# aixplorer_lpc111x.net
KiCad netlist of a schematic drawn in EAGLE
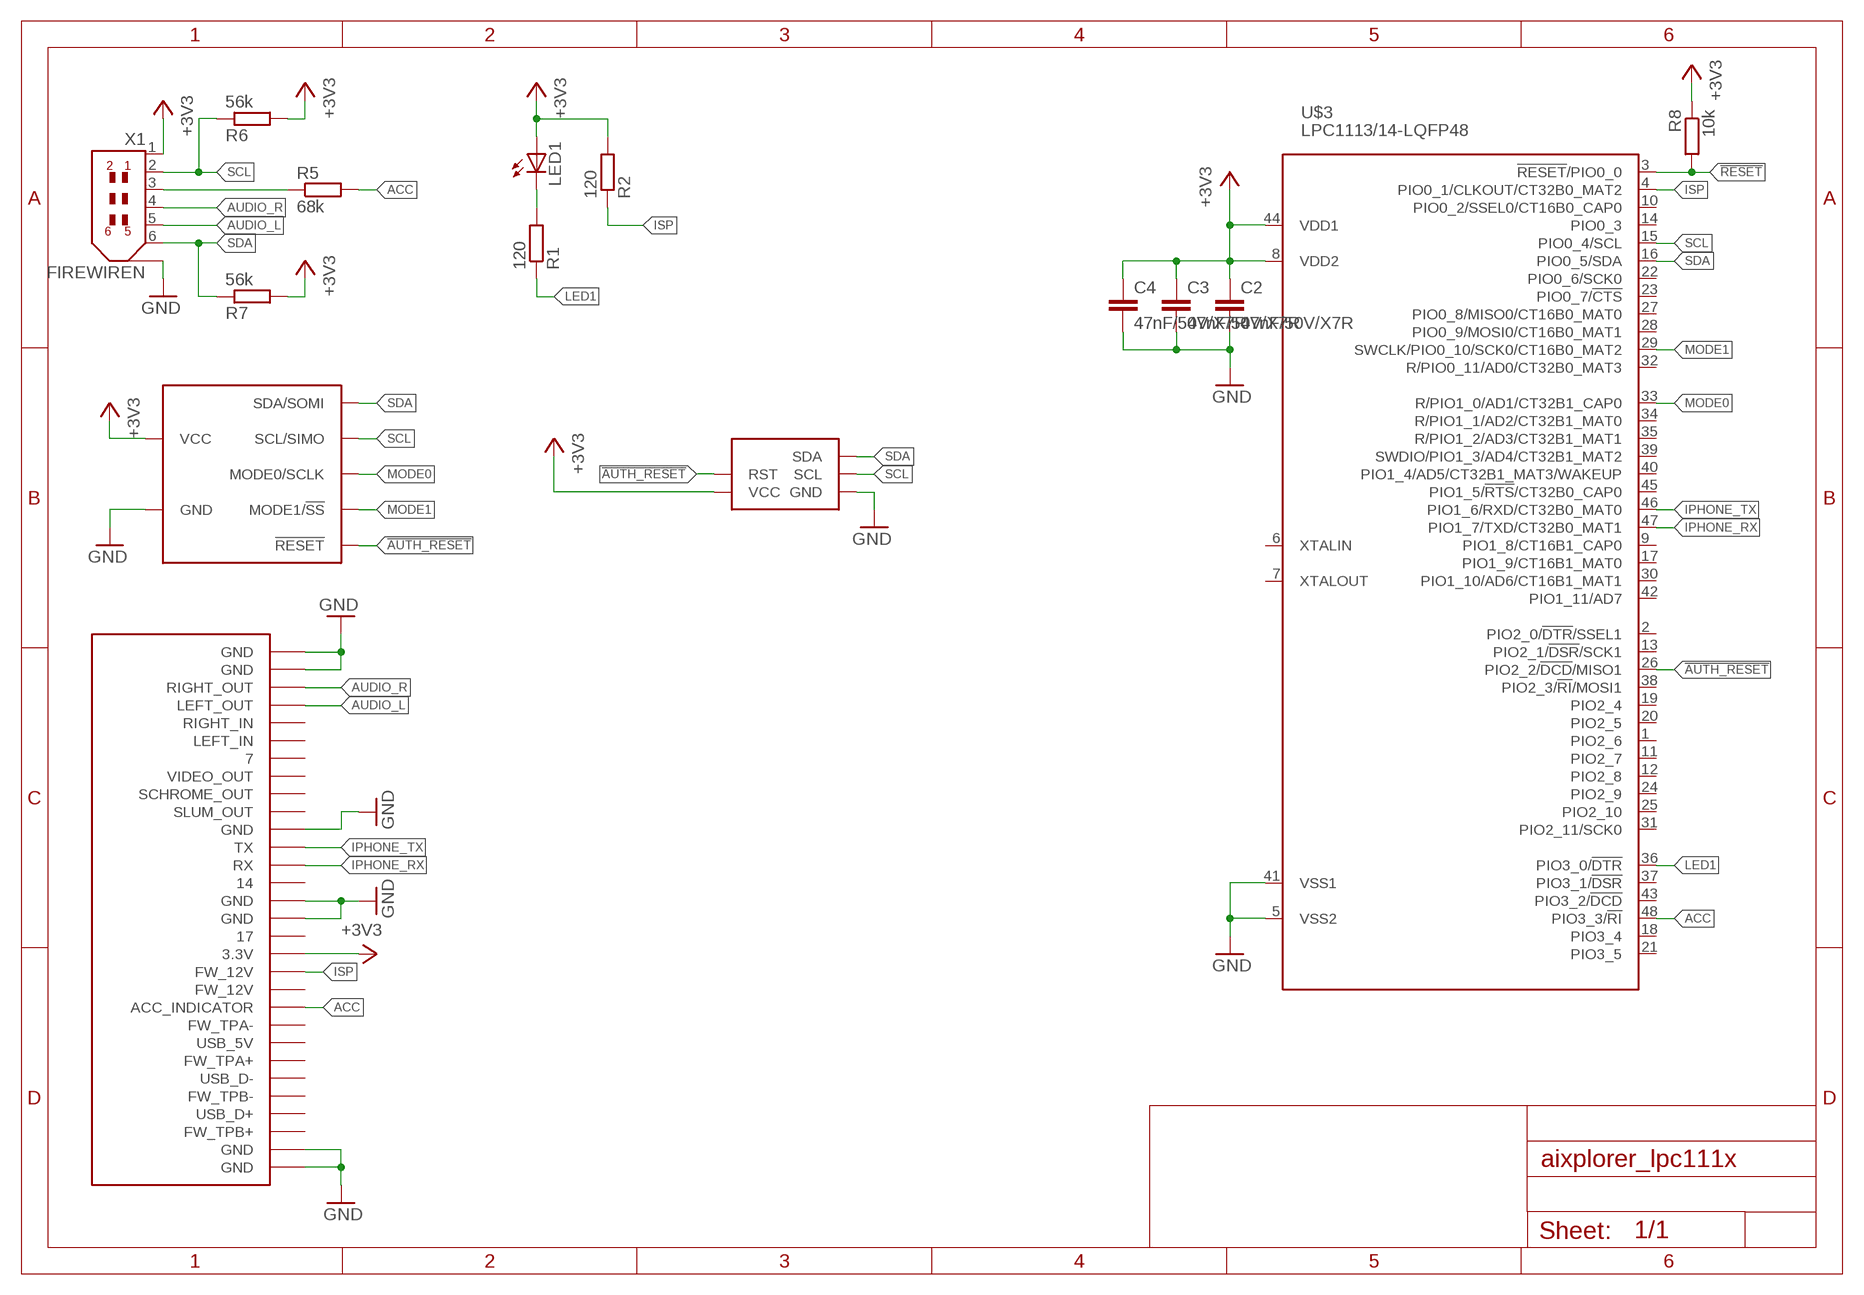
[diagram p0: schematic, sheet 1]

(export (version "E")
  (design (tool "Eeschema 10.0.6"))
  (components
    (comp (ref "C2")
      (value "47nF/50V/X7R")
      (footprint "eagle-import:C0603K")
      (libsource (lib "eagle-import") (part "C-EUC0603K"))
    )
    (comp (ref "C3")
      (value "47nF/50V/X7R")
      (footprint "eagle-import:C0603K")
      (libsource (lib "eagle-import") (part "C-EUC0603K"))
    )
    (comp (ref "C4")
      (value "47nF/50V/X7R")
      (footprint "eagle-import:C0603K")
      (libsource (lib "eagle-import") (part "C-EUC0603K"))
    )
    (comp (ref "LED1")
      (value "LEDCHIPLED_0805")
      (footprint "eagle-import:CHIPLED_0805")
      (libsource (lib "eagle-import") (part "LEDCHIPLED_0805"))
    )
    (comp (ref "R1")
      (value "120")
      (footprint "eagle-import:R0603")
      (libsource (lib "eagle-import") (part "R-EU_R0603"))
    )
    (comp (ref "R2")
      (value "120")
      (footprint "eagle-import:R0603")
      (libsource (lib "eagle-import") (part "R-EU_R0603"))
    )
    (comp (ref "R5")
      (value "68k")
      (footprint "eagle-import:R0603")
      (libsource (lib "eagle-import") (part "R-EU_R0603"))
    )
    (comp (ref "R6")
      (value "56k")
      (footprint "eagle-import:R0603")
      (libsource (lib "eagle-import") (part "R-EU_R0603"))
    )
    (comp (ref "R7")
      (value "56k")
      (footprint "eagle-import:R0603")
      (libsource (lib "eagle-import") (part "R-EU_R0603"))
    )
    (comp (ref "R8")
      (value "10k")
      (footprint "eagle-import:R0603")
      (libsource (lib "eagle-import") (part "R-EU_R0603"))
    )
    (comp (ref "U$1")
      (value "IPAD_CONNECTOR_MALE")
      (footprint "eagle-import:IPOD_CONNECTOR_MALE")
      (libsource (lib "eagle-import") (part "IPAD_CONNECTOR_MALE"))
    )
    (comp (ref "U$2")
      (value "AUTHENTICATORQFN")
      (footprint "eagle-import:AUTH_QFN20")
      (libsource (lib "eagle-import") (part "AUTHENTICATORQFN"))
    )
    (comp (ref "U$3")
      (value "LPC1113/14-LQFP48")
      (footprint "eagle-import:LQFP48")
      (libsource (lib "eagle-import") (part "LPC1113/14-LQFP48"))
    )
    (comp (ref "U$4")
      (value "AUTHENTICATOR_2C")
      (footprint "eagle-import:AUTH_SQC")
      (libsource (lib "eagle-import") (part "AUTHENTICATOR_2C"))
    )
    (comp (ref "X1")
      (value "FIREWIREN")
      (footprint "eagle-import:IEEE1394_90DEG_PINS_NORMAL")
      (libsource (lib "eagle-import") (part "FIREWIREN"))
    )
  )
  (nets
    (net (code "1") (name "+3V3") (class "Default")
      (node (ref "C2") (pin "1") (pinfunction "1_1") (pintype "passive"))
      (node (ref "C3") (pin "1") (pinfunction "1_1") (pintype "passive"))
      (node (ref "C4") (pin "1") (pinfunction "1_1") (pintype "passive"))
      (node (ref "LED1") (pin "A") (pinfunction "A_A") (pintype "passive"))
      (node (ref "R2") (pin "2") (pinfunction "2_2") (pintype "passive"))
      (node (ref "R6") (pin "2") (pinfunction "2_2") (pintype "passive"))
      (node (ref "R7") (pin "2") (pinfunction "2_2") (pintype "passive"))
      (node (ref "R8") (pin "1") (pinfunction "1_1") (pintype "passive"))
      (node (ref "U$1") (pin "P$18") (pinfunction "3.3V_P$18") (pintype "bidirectional"))
      (node (ref "U$2") (pin "P$5") (pinfunction "VCC_P$5") (pintype "bidirectional"))
      (node (ref "U$3") (pin "44") (pinfunction "VDD1_44") (pintype "power_in"))
      (node (ref "U$3") (pin "8") (pinfunction "VDD2_8") (pintype "power_in"))
      (node (ref "U$4") (pin "P$8") (pinfunction "VCC_P$8") (pintype "bidirectional"))
      (node (ref "X1") (pin "1") (pinfunction "1_1") (pintype "passive"))
    )
    (net (code "2") (name "/~{AUTH_RESET}") (class "Default")
      (node (ref "U$2") (pin "P$4") (pinfunction "~{RESET}_P$4") (pintype "bidirectional"))
      (node (ref "U$3") (pin "26") (pinfunction "PIO2_2/~{DCD}/MISO1_26") (pintype "bidirectional"))
      (node (ref "U$4") (pin "P$7") (pinfunction "RST_P$7") (pintype "bidirectional"))
    )
    (net (code "3") (name "/~{RESET}") (class "Default")
      (node (ref "R8") (pin "2") (pinfunction "2_2") (pintype "passive"))
      (node (ref "U$3") (pin "3") (pinfunction "~{RESET}/PIO0_0_3") (pintype "bidirectional"))
    )
    (net (code "4") (name "ACC") (class "Default")
      (node (ref "R5") (pin "2") (pinfunction "2_2") (pintype "passive"))
      (node (ref "U$1") (pin "P$21") (pinfunction "ACC_INDICATOR_P$21") (pintype "bidirectional"))
      (node (ref "U$3") (pin "48") (pinfunction "PIO3_3/~{RI}_48") (pintype "bidirectional"))
    )
    (net (code "5") (name "AUDIO_L") (class "Default")
      (node (ref "U$1") (pin "P$4") (pinfunction "LEFT_OUT_P$4") (pintype "bidirectional"))
      (node (ref "X1") (pin "5") (pinfunction "5_5") (pintype "passive"))
    )
    (net (code "6") (name "AUDIO_R") (class "Default")
      (node (ref "U$1") (pin "P$3") (pinfunction "RIGHT_OUT_P$3") (pintype "bidirectional"))
      (node (ref "X1") (pin "4") (pinfunction "4_4") (pintype "passive"))
    )
    (net (code "7") (name "GND") (class "Default")
      (node (ref "C2") (pin "2") (pinfunction "2_2") (pintype "passive"))
      (node (ref "C3") (pin "2") (pinfunction "2_2") (pintype "passive"))
      (node (ref "C4") (pin "2") (pinfunction "2_2") (pintype "passive"))
      (node (ref "U$1") (pin "P$1") (pinfunction "GND_P$1") (pintype "bidirectional"))
      (node (ref "U$1") (pin "P$11") (pinfunction "GND_P$11") (pintype "bidirectional"))
      (node (ref "U$1") (pin "P$15") (pinfunction "GND_P$15") (pintype "bidirectional"))
      (node (ref "U$1") (pin "P$16") (pinfunction "GND_P$16") (pintype "bidirectional"))
      (node (ref "U$1") (pin "P$2") (pinfunction "GND_P$2") (pintype "bidirectional"))
      (node (ref "U$1") (pin "P$29") (pinfunction "GND_P$29") (pintype "bidirectional"))
      (node (ref "U$1") (pin "P$30") (pinfunction "GND_P$30") (pintype "bidirectional"))
      (node (ref "U$2") (pin "P$11") (pinfunction "GND_P$11") (pintype "bidirectional"))
      (node (ref "U$3") (pin "41") (pinfunction "VSS1_41") (pintype "power_in"))
      (node (ref "U$3") (pin "5") (pinfunction "VSS2_5") (pintype "power_in"))
      (node (ref "U$4") (pin "P$1") (pinfunction "GND_P$1") (pintype "bidirectional"))
      (node (ref "X1") (pin "M1") (pinfunction "7_M1") (pintype "passive"))
      (node (ref "X1") (pin "M2") (pinfunction "7_M2") (pintype "passive"))
    )
    (net (code "8") (name "IPHONE_RX") (class "Default")
      (node (ref "U$1") (pin "P$13") (pinfunction "RX_P$13") (pintype "bidirectional"))
      (node (ref "U$3") (pin "47") (pinfunction "PIO1_7/TXD/CT32B0_MAT1_47") (pintype "bidirectional"))
    )
    (net (code "9") (name "IPHONE_TX") (class "Default")
      (node (ref "U$1") (pin "P$12") (pinfunction "TX_P$12") (pintype "bidirectional"))
      (node (ref "U$3") (pin "46") (pinfunction "PIO1_6/RXD/CT32B0_MAT0_46") (pintype "bidirectional"))
    )
    (net (code "10") (name "ISP") (class "Default")
      (node (ref "R2") (pin "1") (pinfunction "1_1") (pintype "passive"))
      (node (ref "U$1") (pin "P$19") (pinfunction "FW_12V_P$19") (pintype "bidirectional"))
      (node (ref "U$3") (pin "4") (pinfunction "PIO0_1/CLKOUT/CT32B0_MAT2_4") (pintype "bidirectional"))
    )
    (net (code "11") (name "LED1") (class "Default")
      (node (ref "R1") (pin "1") (pinfunction "1_1") (pintype "passive"))
      (node (ref "U$3") (pin "36") (pinfunction "PIO3_0/~{DTR}_36") (pintype "bidirectional"))
    )
    (net (code "12") (name "MODE0") (class "Default")
      (node (ref "U$2") (pin "P$14") (pinfunction "MODE0/SCLK_P$14") (pintype "bidirectional"))
      (node (ref "U$3") (pin "33") (pinfunction "R/PIO1_0/AD1/CT32B1_CAP0_33") (pintype "bidirectional"))
    )
    (net (code "13") (name "MODE1") (class "Default")
      (node (ref "U$2") (pin "P$2") (pinfunction "MODE1/~{SS}_P$2") (pintype "bidirectional"))
      (node (ref "U$3") (pin "29") (pinfunction "SWCLK/PIO0_10/SCK0/CT16B0_MAT2_29") (pintype "bidirectional"))
    )
    (net (code "14") (name "Net-(LED1-PadC)") (class "Default")
      (node (ref "LED1") (pin "C") (pinfunction "C_C") (pintype "passive"))
      (node (ref "R1") (pin "2") (pinfunction "2_2") (pintype "passive"))
    )
    (net (code "15") (name "Net-(R5-Pad1)") (class "Default")
      (node (ref "R5") (pin "1") (pinfunction "1_1") (pintype "passive"))
      (node (ref "X1") (pin "3") (pinfunction "3_3") (pintype "passive"))
    )
    (net (code "16") (name "SCL") (class "Default")
      (node (ref "R6") (pin "1") (pinfunction "1_1") (pintype "passive"))
      (node (ref "U$2") (pin "P$12") (pinfunction "SCL/SIMO_P$12") (pintype "bidirectional"))
      (node (ref "U$3") (pin "15") (pinfunction "PIO0_4/SCL_15") (pintype "bidirectional"))
      (node (ref "U$4") (pin "P$6") (pinfunction "SCL_P$6") (pintype "bidirectional"))
      (node (ref "X1") (pin "2") (pinfunction "2_2") (pintype "passive"))
    )
    (net (code "17") (name "SDA") (class "Default")
      (node (ref "R7") (pin "1") (pinfunction "1_1") (pintype "passive"))
      (node (ref "U$2") (pin "P$13") (pinfunction "SDA/SOMI_P$13") (pintype "bidirectional"))
      (node (ref "U$3") (pin "16") (pinfunction "PIO0_5/SDA_16") (pintype "bidirectional"))
      (node (ref "U$4") (pin "P$2") (pinfunction "SDA_P$2") (pintype "bidirectional"))
      (node (ref "X1") (pin "6") (pinfunction "6_6") (pintype "passive"))
    )
    (net (code "18") (name "unconnected-(U$1-7-PadP$7)") (class "Default")
      (node (ref "U$1") (pin "P$7") (pinfunction "7_P$7") (pintype "bidirectional"))
    )
    (net (code "19") (name "unconnected-(U$1-14-PadP$14)") (class "Default")
      (node (ref "U$1") (pin "P$14") (pinfunction "14_P$14") (pintype "bidirectional"))
    )
    (net (code "20") (name "unconnected-(U$1-17-PadP$17)") (class "Default")
      (node (ref "U$1") (pin "P$17") (pinfunction "17_P$17") (pintype "bidirectional"))
    )
    (net (code "21") (name "unconnected-(U$1-FW_12V-PadP$20)") (class "Default")
      (node (ref "U$1") (pin "P$20") (pinfunction "FW_12V_P$20") (pintype "bidirectional"))
    )
    (net (code "22") (name "unconnected-(U$1-FW_TPA+-PadP$24)") (class "Default")
      (node (ref "U$1") (pin "P$24") (pinfunction "FW_TPA+_P$24") (pintype "bidirectional"))
    )
    (net (code "23") (name "unconnected-(U$1-FW_TPA--PadP$22)") (class "Default")
      (node (ref "U$1") (pin "P$22") (pinfunction "FW_TPA-_P$22") (pintype "bidirectional"))
    )
    (net (code "24") (name "unconnected-(U$1-FW_TPB+-PadP$28)") (class "Default")
      (node (ref "U$1") (pin "P$28") (pinfunction "FW_TPB+_P$28") (pintype "bidirectional"))
    )
    (net (code "25") (name "unconnected-(U$1-FW_TPB--PadP$26)") (class "Default")
      (node (ref "U$1") (pin "P$26") (pinfunction "FW_TPB-_P$26") (pintype "bidirectional"))
    )
    (net (code "26") (name "unconnected-(U$1-LEFT_IN-PadP$6)") (class "Default")
      (node (ref "U$1") (pin "P$6") (pinfunction "LEFT_IN_P$6") (pintype "bidirectional"))
    )
    (net (code "27") (name "unconnected-(U$1-RIGHT_IN-PadP$5)") (class "Default")
      (node (ref "U$1") (pin "P$5") (pinfunction "RIGHT_IN_P$5") (pintype "bidirectional"))
    )
    (net (code "28") (name "unconnected-(U$1-SCHROME_OUT-PadP$9)") (class "Default")
      (node (ref "U$1") (pin "P$9") (pinfunction "SCHROME_OUT_P$9") (pintype "bidirectional"))
    )
    (net (code "29") (name "unconnected-(U$1-SLUM_OUT-PadP$10)") (class "Default")
      (node (ref "U$1") (pin "P$10") (pinfunction "SLUM_OUT_P$10") (pintype "bidirectional"))
    )
    (net (code "30") (name "unconnected-(U$1-USB_5V-PadP$23)") (class "Default")
      (node (ref "U$1") (pin "P$23") (pinfunction "USB_5V_P$23") (pintype "bidirectional"))
    )
    (net (code "31") (name "unconnected-(U$1-USB_D+-PadP$27)") (class "Default")
      (node (ref "U$1") (pin "P$27") (pinfunction "USB_D+_P$27") (pintype "bidirectional"))
    )
    (net (code "32") (name "unconnected-(U$1-USB_D--PadP$25)") (class "Default")
      (node (ref "U$1") (pin "P$25") (pinfunction "USB_D-_P$25") (pintype "bidirectional"))
    )
    (net (code "33") (name "unconnected-(U$1-VIDEO_OUT-PadP$8)") (class "Default")
      (node (ref "U$1") (pin "P$8") (pinfunction "VIDEO_OUT_P$8") (pintype "bidirectional"))
    )
    (net (code "34") (name "unconnected-(U$3-PIO0_2{slash}SSEL0{slash}CT16B0_CAP0-Pad10)") (class "Default")
      (node (ref "U$3") (pin "10") (pinfunction "PIO0_2/SSEL0/CT16B0_CAP0_10") (pintype "bidirectional"))
    )
    (net (code "35") (name "unconnected-(U$3-PIO0_3-Pad14)") (class "Default")
      (node (ref "U$3") (pin "14") (pinfunction "PIO0_3_14") (pintype "bidirectional"))
    )
    (net (code "36") (name "unconnected-(U$3-PIO0_6{slash}SCK0-Pad22)") (class "Default")
      (node (ref "U$3") (pin "22") (pinfunction "PIO0_6/SCK0_22") (pintype "bidirectional"))
    )
    (net (code "37") (name "unconnected-(U$3-PIO0_7{slash}~{CTS}-Pad23)") (class "Default")
      (node (ref "U$3") (pin "23") (pinfunction "PIO0_7/~{CTS}_23") (pintype "bidirectional"))
    )
    (net (code "38") (name "unconnected-(U$3-PIO0_8{slash}MISO0{slash}CT16B0_MAT0-Pad27)") (class "Default")
      (node (ref "U$3") (pin "27") (pinfunction "PIO0_8/MISO0/CT16B0_MAT0_27") (pintype "bidirectional"))
    )
    (net (code "39") (name "unconnected-(U$3-PIO0_9{slash}MOSI0{slash}CT16B0_MAT1-Pad28)") (class "Default")
      (node (ref "U$3") (pin "28") (pinfunction "PIO0_9/MOSI0/CT16B0_MAT1_28") (pintype "bidirectional"))
    )
    (net (code "40") (name "unconnected-(U$3-PIO1_4{slash}AD5{slash}CT32B1_MAT3{slash}WAKEUP-Pad40)") (class "Default")
      (node (ref "U$3") (pin "40") (pinfunction "PIO1_4/AD5/CT32B1_MAT3/WAKEUP_40") (pintype "bidirectional"))
    )
    (net (code "41") (name "unconnected-(U$3-PIO1_5{slash}~{RTS}{slash}CT32B0_CAP0-Pad45)") (class "Default")
      (node (ref "U$3") (pin "45") (pinfunction "PIO1_5/~{RTS}/CT32B0_CAP0_45") (pintype "bidirectional"))
    )
    (net (code "42") (name "unconnected-(U$3-PIO1_8{slash}CT16B1_CAP0-Pad9)") (class "Default")
      (node (ref "U$3") (pin "9") (pinfunction "PIO1_8/CT16B1_CAP0_9") (pintype "bidirectional"))
    )
    (net (code "43") (name "unconnected-(U$3-PIO1_9{slash}CT16B1_MAT0-Pad17)") (class "Default")
      (node (ref "U$3") (pin "17") (pinfunction "PIO1_9/CT16B1_MAT0_17") (pintype "bidirectional"))
    )
    (net (code "44") (name "unconnected-(U$3-PIO1_10{slash}AD6{slash}CT16B1_MAT1-Pad30)") (class "Default")
      (node (ref "U$3") (pin "30") (pinfunction "PIO1_10/AD6/CT16B1_MAT1_30") (pintype "bidirectional"))
    )
    (net (code "45") (name "unconnected-(U$3-PIO1_11{slash}AD7-Pad42)") (class "Default")
      (node (ref "U$3") (pin "42") (pinfunction "PIO1_11/AD7_42") (pintype "bidirectional"))
    )
    (net (code "46") (name "unconnected-(U$3-PIO2_0{slash}~{DTR}{slash}SSEL1-Pad2)") (class "Default")
      (node (ref "U$3") (pin "2") (pinfunction "PIO2_0/~{DTR}/SSEL1_2") (pintype "bidirectional"))
    )
    (net (code "47") (name "unconnected-(U$3-PIO2_1{slash}~{DSR}{slash}SCK1-Pad13)") (class "Default")
      (node (ref "U$3") (pin "13") (pinfunction "PIO2_1/~{DSR}/SCK1_13") (pintype "bidirectional"))
    )
    (net (code "48") (name "unconnected-(U$3-PIO2_3{slash}~{RI}{slash}MOSI1-Pad38)") (class "Default")
      (node (ref "U$3") (pin "38") (pinfunction "PIO2_3/~{RI}/MOSI1_38") (pintype "bidirectional"))
    )
    (net (code "49") (name "unconnected-(U$3-PIO2_4-Pad19)") (class "Default")
      (node (ref "U$3") (pin "19") (pinfunction "PIO2_4_19") (pintype "bidirectional"))
    )
    (net (code "50") (name "unconnected-(U$3-PIO2_5-Pad20)") (class "Default")
      (node (ref "U$3") (pin "20") (pinfunction "PIO2_5_20") (pintype "bidirectional"))
    )
    (net (code "51") (name "unconnected-(U$3-PIO2_6-Pad1)") (class "Default")
      (node (ref "U$3") (pin "1") (pinfunction "PIO2_6_1") (pintype "bidirectional"))
    )
    (net (code "52") (name "unconnected-(U$3-PIO2_7-Pad11)") (class "Default")
      (node (ref "U$3") (pin "11") (pinfunction "PIO2_7_11") (pintype "bidirectional"))
    )
    (net (code "53") (name "unconnected-(U$3-PIO2_8-Pad12)") (class "Default")
      (node (ref "U$3") (pin "12") (pinfunction "PIO2_8_12") (pintype "bidirectional"))
    )
    (net (code "54") (name "unconnected-(U$3-PIO2_9-Pad24)") (class "Default")
      (node (ref "U$3") (pin "24") (pinfunction "PIO2_9_24") (pintype "bidirectional"))
    )
    (net (code "55") (name "unconnected-(U$3-PIO2_10-Pad25)") (class "Default")
      (node (ref "U$3") (pin "25") (pinfunction "PIO2_10_25") (pintype "bidirectional"))
    )
    (net (code "56") (name "unconnected-(U$3-PIO2_11{slash}SCK0-Pad31)") (class "Default")
      (node (ref "U$3") (pin "31") (pinfunction "PIO2_11/SCK0_31") (pintype "bidirectional"))
    )
    (net (code "57") (name "unconnected-(U$3-PIO3_1{slash}~{DSR}-Pad37)") (class "Default")
      (node (ref "U$3") (pin "37") (pinfunction "PIO3_1/~{DSR}_37") (pintype "bidirectional"))
    )
    (net (code "58") (name "unconnected-(U$3-PIO3_2{slash}~{DCD}-Pad43)") (class "Default")
      (node (ref "U$3") (pin "43") (pinfunction "PIO3_2/~{DCD}_43") (pintype "bidirectional"))
    )
    (net (code "59") (name "unconnected-(U$3-PIO3_4-Pad18)") (class "Default")
      (node (ref "U$3") (pin "18") (pinfunction "PIO3_4_18") (pintype "bidirectional"))
    )
    (net (code "60") (name "unconnected-(U$3-PIO3_5-Pad21)") (class "Default")
      (node (ref "U$3") (pin "21") (pinfunction "PIO3_5_21") (pintype "bidirectional"))
    )
    (net (code "61") (name "unconnected-(U$3-R{slash}PIO0_11{slash}AD0{slash}CT32B0_MAT3-Pad32)") (class "Default")
      (node (ref "U$3") (pin "32") (pinfunction "R/PIO0_11/AD0/CT32B0_MAT3_32") (pintype "bidirectional"))
    )
    (net (code "62") (name "unconnected-(U$3-R{slash}PIO1_1{slash}AD2{slash}CT32B1_MAT0-Pad34)") (class "Default")
      (node (ref "U$3") (pin "34") (pinfunction "R/PIO1_1/AD2/CT32B1_MAT0_34") (pintype "bidirectional"))
    )
    (net (code "63") (name "unconnected-(U$3-R{slash}PIO1_2{slash}AD3{slash}CT32B1_MAT1-Pad35)") (class "Default")
      (node (ref "U$3") (pin "35") (pinfunction "R/PIO1_2/AD3/CT32B1_MAT1_35") (pintype "bidirectional"))
    )
    (net (code "64") (name "unconnected-(U$3-SWDIO{slash}PIO1_3{slash}AD4{slash}CT32B1_MAT2-Pad39)") (class "Default")
      (node (ref "U$3") (pin "39") (pinfunction "SWDIO/PIO1_3/AD4/CT32B1_MAT2_39") (pintype "bidirectional"))
    )
    (net (code "65") (name "unconnected-(U$3-XTALIN-Pad6)") (class "Default")
      (node (ref "U$3") (pin "6") (pinfunction "XTALIN_6") (pintype "passive"))
    )
    (net (code "66") (name "unconnected-(U$3-XTALOUT-Pad7)") (class "Default")
      (node (ref "U$3") (pin "7") (pinfunction "XTALOUT_7") (pintype "passive"))
    )
  )
)
